# Motor_External_Connectors.net
KiCad netlist of a schematic drawn in Altium Designer
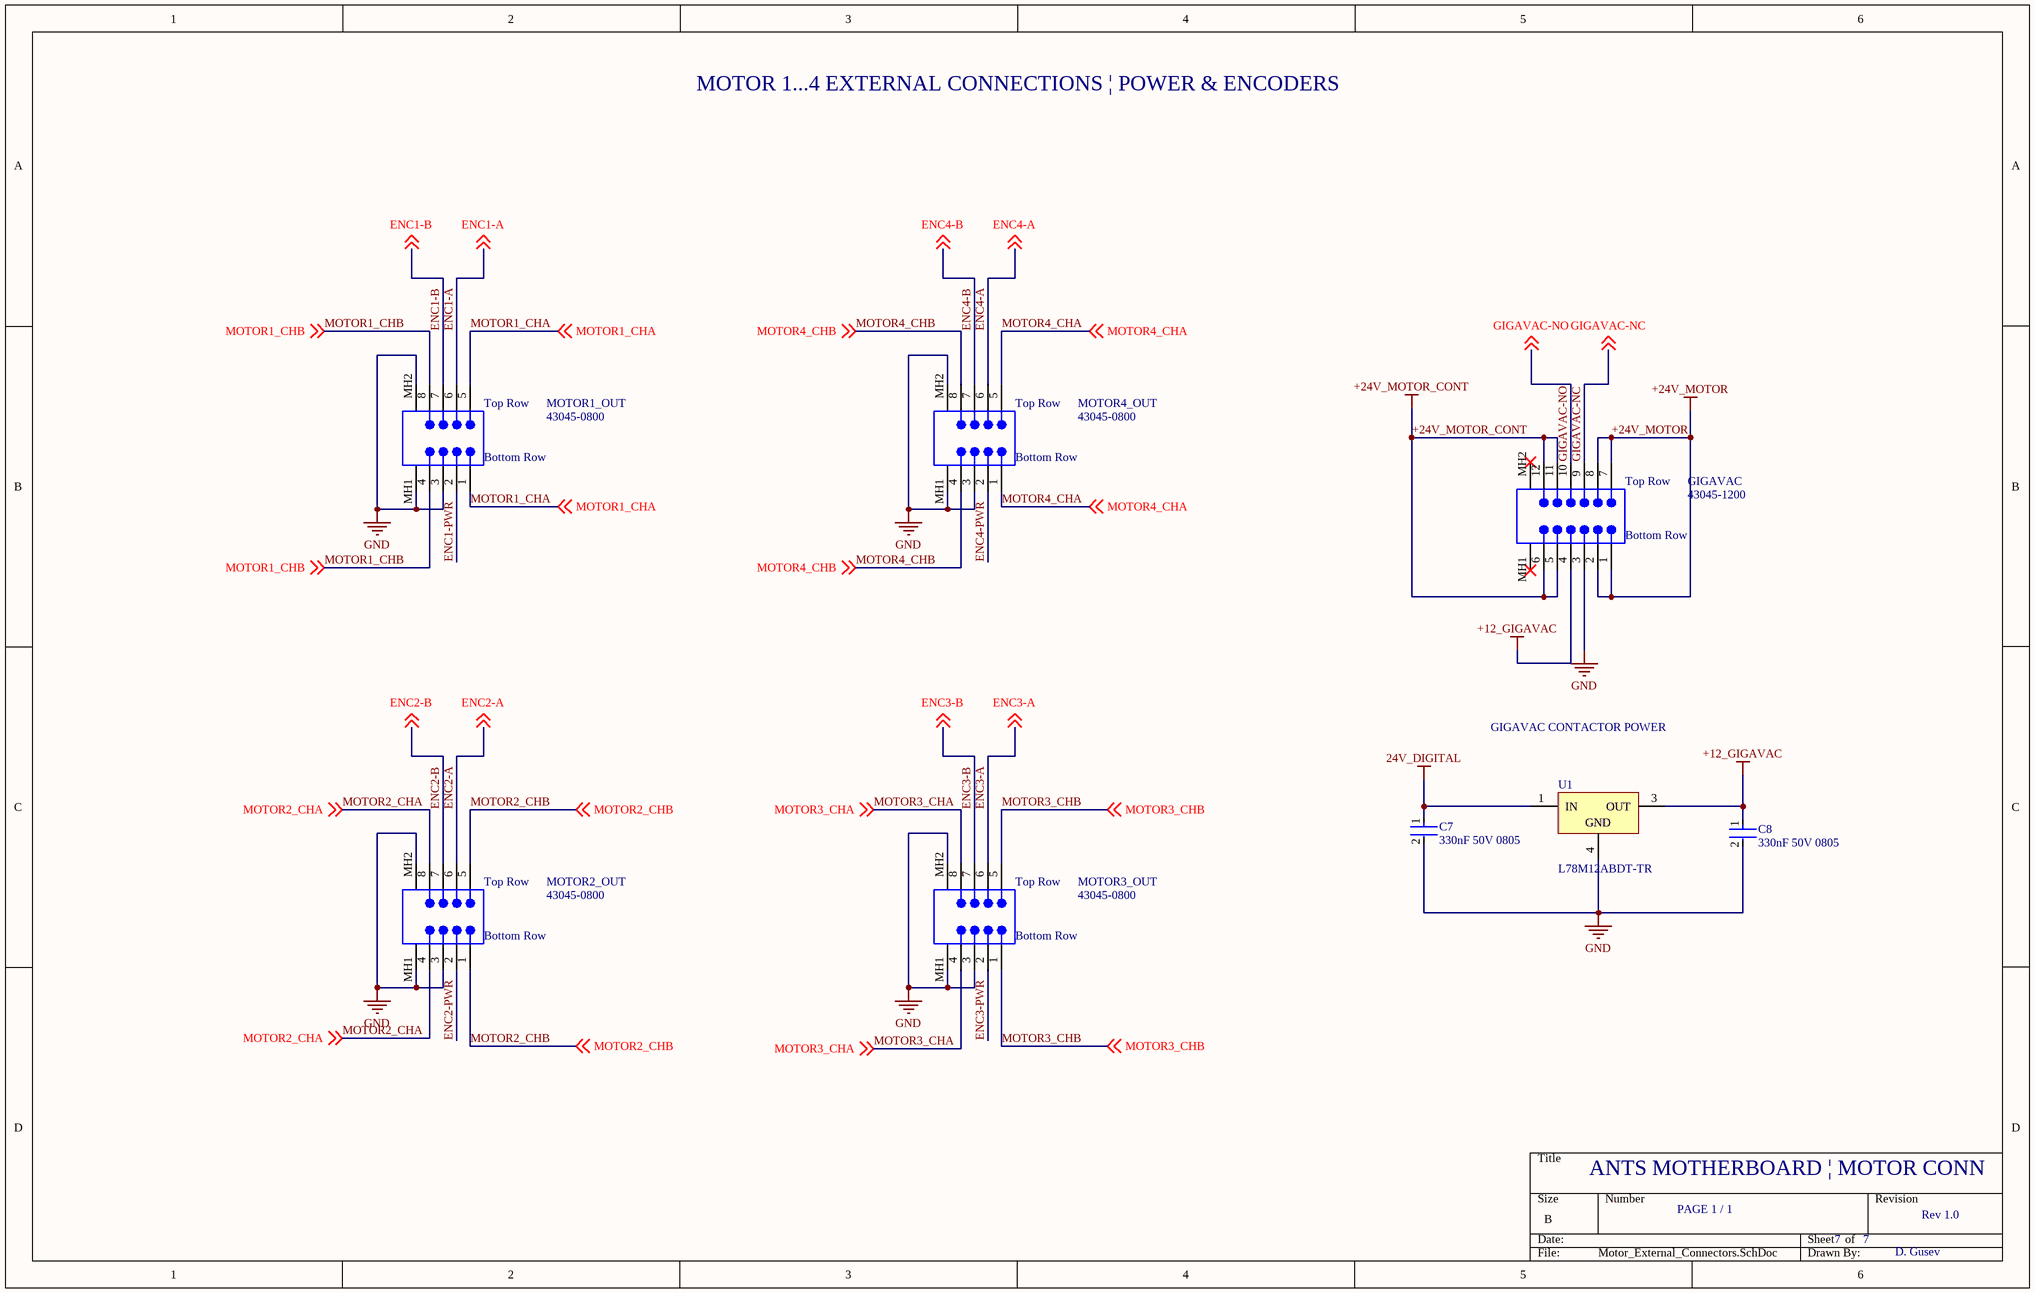
[diagram p0: Motor_External_Connectors.SchDoc]

(export (version "E")
  (design (tool "Eeschema 10.0.6"))
  (components
    (comp (ref "C7")
      (value "330nF 50V 0805")
      (footprint "FP-C0805C-DN-MFG")
      (description "CAP CER 0.33UF 50V X7R 0805")
      (fields
        (field (name "MANUFACTURER PART NUMBER") "C0805C334K5RACTU")
        (field (name "MANUFACTURER") "KEMET")
      )
      (libsource (lib "Altium Content Vault") (part "b4654b650e69147ec39a6b967a45e02"))
    )
    (comp (ref "C8")
      (value "330nF 50V 0805")
      (footprint "FP-C0805C-DN-MFG")
      (description "CAP CER 0.33UF 50V X7R 0805")
      (fields
        (field (name "MANUFACTURER PART NUMBER") "C0805C334K5RACTU")
        (field (name "MANUFACTURER") "KEMET")
      )
      (libsource (lib "Altium Content Vault") (part "b4654b650e69147ec39a6b967a45e02"))
    )
    (comp (ref "GIGAVAC")
      (value "43045-1200")
      (footprint "MOLX-43045-1200")
      (fields (field (name "PARTNUMBER") "43045-0812"))
      (libsource (lib "ANTS-MotherBoard-B1") (part "Molex 0430451-200"))
    )
    (comp (ref "MOTOR1_OUT")
      (value "43045-0800")
      (footprint "MOLX-43045-0800")
      (fields (field (name "PARTNUMBER") "43045-0812"))
      (libsource (lib "ANTS-MotherBoard-B1") (part "Molex 0430450-800"))
    )
    (comp (ref "MOTOR2_OUT")
      (value "43045-0800")
      (footprint "MOLX-43045-0800")
      (fields (field (name "PARTNUMBER") "43045-0812"))
      (libsource (lib "ANTS-MotherBoard-B1") (part "Molex 0430450-800"))
    )
    (comp (ref "MOTOR3_OUT")
      (value "43045-0800")
      (footprint "MOLX-43045-0800")
      (fields (field (name "PARTNUMBER") "43045-0812"))
      (libsource (lib "ANTS-MotherBoard-B1") (part "Molex 0430450-800"))
    )
    (comp (ref "MOTOR4_OUT")
      (value "43045-0800")
      (footprint "MOLX-43045-0800")
      (fields (field (name "PARTNUMBER") "43045-0812"))
      (libsource (lib "ANTS-MotherBoard-B1") (part "Molex 0430450-800"))
    )
    (comp (ref "U1")
      (value "L78M12ABDT-TR")
      (footprint "TO-252_M")
      (description "Precision 500mA Regulator, 12V, 3-Pin DPAK, Tape and Reel")
      (libsource (lib "Altium Content Vault") (part "PM-REG-L4940-SOT3"))
    )
  )
  (nets
    (net (code "1") (name "+12_GIGAVAC") (class "Default")
      (node (ref "C8") (pin "1") (pinfunction "1_1") (pintype "passive"))
      (node (ref "GIGAVAC") (pin "4") (pinfunction "4_4") (pintype "passive"))
      (node (ref "U1") (pin "3") (pinfunction "OUT_3") (pintype "power_in"))
    )
    (net (code "2") (name "+24V_MOTOR") (class "Default")
      (node (ref "GIGAVAC") (pin "1") (pinfunction "1_1") (pintype "passive"))
      (node (ref "GIGAVAC") (pin "2") (pinfunction "2_2") (pintype "passive"))
      (node (ref "GIGAVAC") (pin "7") (pinfunction "7_7") (pintype "passive"))
      (node (ref "GIGAVAC") (pin "8") (pinfunction "8_8") (pintype "passive"))
    )
    (net (code "3") (name "+24V_MOTOR_CONT") (class "Default")
      (node (ref "GIGAVAC") (pin "11") (pinfunction "11_11") (pintype "passive"))
      (node (ref "GIGAVAC") (pin "12") (pinfunction "12_12") (pintype "passive"))
      (node (ref "GIGAVAC") (pin "5") (pinfunction "5_5") (pintype "passive"))
      (node (ref "GIGAVAC") (pin "6") (pinfunction "6_6") (pintype "passive"))
    )
    (net (code "4") (name "/ENC1-PWR") (class "Default")
      (node (ref "MOTOR1_OUT") (pin "2") (pinfunction "2_2") (pintype "passive"))
    )
    (net (code "5") (name "/ENC2-PWR") (class "Default")
      (node (ref "MOTOR2_OUT") (pin "2") (pinfunction "2_2") (pintype "passive"))
    )
    (net (code "6") (name "/ENC3-PWR") (class "Default")
      (node (ref "MOTOR3_OUT") (pin "2") (pinfunction "2_2") (pintype "passive"))
    )
    (net (code "7") (name "/ENC4-PWR") (class "Default")
      (node (ref "MOTOR4_OUT") (pin "2") (pinfunction "2_2") (pintype "passive"))
    )
    (net (code "8") (name "24V_DIGITAL") (class "Default")
      (node (ref "C7") (pin "1") (pinfunction "1_1") (pintype "passive"))
      (node (ref "U1") (pin "1") (pinfunction "IN_1") (pintype "power_in"))
    )
    (net (code "9") (name "ENC1-A") (class "Default")
      (node (ref "MOTOR1_OUT") (pin "6") (pinfunction "6_6") (pintype "passive"))
    )
    (net (code "10") (name "ENC1-B") (class "Default")
      (node (ref "MOTOR1_OUT") (pin "7") (pinfunction "7_7") (pintype "passive"))
    )
    (net (code "11") (name "ENC2-A") (class "Default")
      (node (ref "MOTOR2_OUT") (pin "6") (pinfunction "6_6") (pintype "passive"))
    )
    (net (code "12") (name "ENC2-B") (class "Default")
      (node (ref "MOTOR2_OUT") (pin "7") (pinfunction "7_7") (pintype "passive"))
    )
    (net (code "13") (name "ENC3-A") (class "Default")
      (node (ref "MOTOR3_OUT") (pin "6") (pinfunction "6_6") (pintype "passive"))
    )
    (net (code "14") (name "ENC3-B") (class "Default")
      (node (ref "MOTOR3_OUT") (pin "7") (pinfunction "7_7") (pintype "passive"))
    )
    (net (code "15") (name "ENC4-A") (class "Default")
      (node (ref "MOTOR4_OUT") (pin "6") (pinfunction "6_6") (pintype "passive"))
    )
    (net (code "16") (name "ENC4-B") (class "Default")
      (node (ref "MOTOR4_OUT") (pin "7") (pinfunction "7_7") (pintype "passive"))
    )
    (net (code "17") (name "GIGAVAC-NC") (class "Default")
      (node (ref "GIGAVAC") (pin "9") (pinfunction "9_9") (pintype "passive"))
    )
    (net (code "18") (name "GIGAVAC-NO") (class "Default")
      (node (ref "GIGAVAC") (pin "10") (pinfunction "10_10") (pintype "passive"))
    )
    (net (code "19") (name "GND") (class "Default")
      (node (ref "C7") (pin "2") (pinfunction "2_2") (pintype "passive"))
      (node (ref "C8") (pin "2") (pinfunction "2_2") (pintype "passive"))
      (node (ref "GIGAVAC") (pin "3") (pinfunction "3_3") (pintype "passive"))
      (node (ref "MOTOR1_OUT") (pin "3") (pinfunction "3_3") (pintype "passive"))
      (node (ref "MOTOR1_OUT") (pin "MH1") (pinfunction "MH1_MH1") (pintype "passive"))
      (node (ref "MOTOR1_OUT") (pin "MH2") (pinfunction "MH2_MH2") (pintype "passive"))
      (node (ref "MOTOR2_OUT") (pin "3") (pinfunction "3_3") (pintype "passive"))
      (node (ref "MOTOR2_OUT") (pin "MH1") (pinfunction "MH1_MH1") (pintype "passive"))
      (node (ref "MOTOR2_OUT") (pin "MH2") (pinfunction "MH2_MH2") (pintype "passive"))
      (node (ref "MOTOR3_OUT") (pin "3") (pinfunction "3_3") (pintype "passive"))
      (node (ref "MOTOR3_OUT") (pin "MH1") (pinfunction "MH1_MH1") (pintype "passive"))
      (node (ref "MOTOR3_OUT") (pin "MH2") (pinfunction "MH2_MH2") (pintype "passive"))
      (node (ref "MOTOR4_OUT") (pin "3") (pinfunction "3_3") (pintype "passive"))
      (node (ref "MOTOR4_OUT") (pin "MH1") (pinfunction "MH1_MH1") (pintype "passive"))
      (node (ref "MOTOR4_OUT") (pin "MH2") (pinfunction "MH2_MH2") (pintype "passive"))
      (node (ref "U1") (pin "4") (pinfunction "GND_4") (pintype "power_in"))
    )
    (net (code "20") (name "MOTOR1_CHA") (class "Default")
      (node (ref "MOTOR1_OUT") (pin "1") (pinfunction "1_1") (pintype "passive"))
      (node (ref "MOTOR1_OUT") (pin "5") (pinfunction "5_5") (pintype "passive"))
    )
    (net (code "21") (name "MOTOR1_CHB") (class "Default")
      (node (ref "MOTOR1_OUT") (pin "4") (pinfunction "4_4") (pintype "passive"))
      (node (ref "MOTOR1_OUT") (pin "8") (pinfunction "8_8") (pintype "passive"))
    )
    (net (code "22") (name "MOTOR2_CHA") (class "Default")
      (node (ref "MOTOR2_OUT") (pin "4") (pinfunction "4_4") (pintype "passive"))
      (node (ref "MOTOR2_OUT") (pin "8") (pinfunction "8_8") (pintype "passive"))
    )
    (net (code "23") (name "MOTOR2_CHB") (class "Default")
      (node (ref "MOTOR2_OUT") (pin "1") (pinfunction "1_1") (pintype "passive"))
      (node (ref "MOTOR2_OUT") (pin "5") (pinfunction "5_5") (pintype "passive"))
    )
    (net (code "24") (name "MOTOR3_CHA") (class "Default")
      (node (ref "MOTOR3_OUT") (pin "4") (pinfunction "4_4") (pintype "passive"))
      (node (ref "MOTOR3_OUT") (pin "8") (pinfunction "8_8") (pintype "passive"))
    )
    (net (code "25") (name "MOTOR3_CHB") (class "Default")
      (node (ref "MOTOR3_OUT") (pin "1") (pinfunction "1_1") (pintype "passive"))
      (node (ref "MOTOR3_OUT") (pin "5") (pinfunction "5_5") (pintype "passive"))
    )
    (net (code "26") (name "MOTOR4_CHA") (class "Default")
      (node (ref "MOTOR4_OUT") (pin "1") (pinfunction "1_1") (pintype "passive"))
      (node (ref "MOTOR4_OUT") (pin "5") (pinfunction "5_5") (pintype "passive"))
    )
    (net (code "27") (name "MOTOR4_CHB") (class "Default")
      (node (ref "MOTOR4_OUT") (pin "4") (pinfunction "4_4") (pintype "passive"))
      (node (ref "MOTOR4_OUT") (pin "8") (pinfunction "8_8") (pintype "passive"))
    )
    (net (code "28") (name "unconnected-(GIGAVAC-PadMH1)") (class "Default")
      (node (ref "GIGAVAC") (pin "MH1") (pinfunction "MH1_MH1") (pintype "passive+no_connect"))
    )
    (net (code "29") (name "unconnected-(GIGAVAC-PadMH2)") (class "Default")
      (node (ref "GIGAVAC") (pin "MH2") (pinfunction "MH2_MH2") (pintype "passive+no_connect"))
    )
  )
)
